# STM32F107_207.net
KiCad netlist of a schematic drawn in Altium Designer
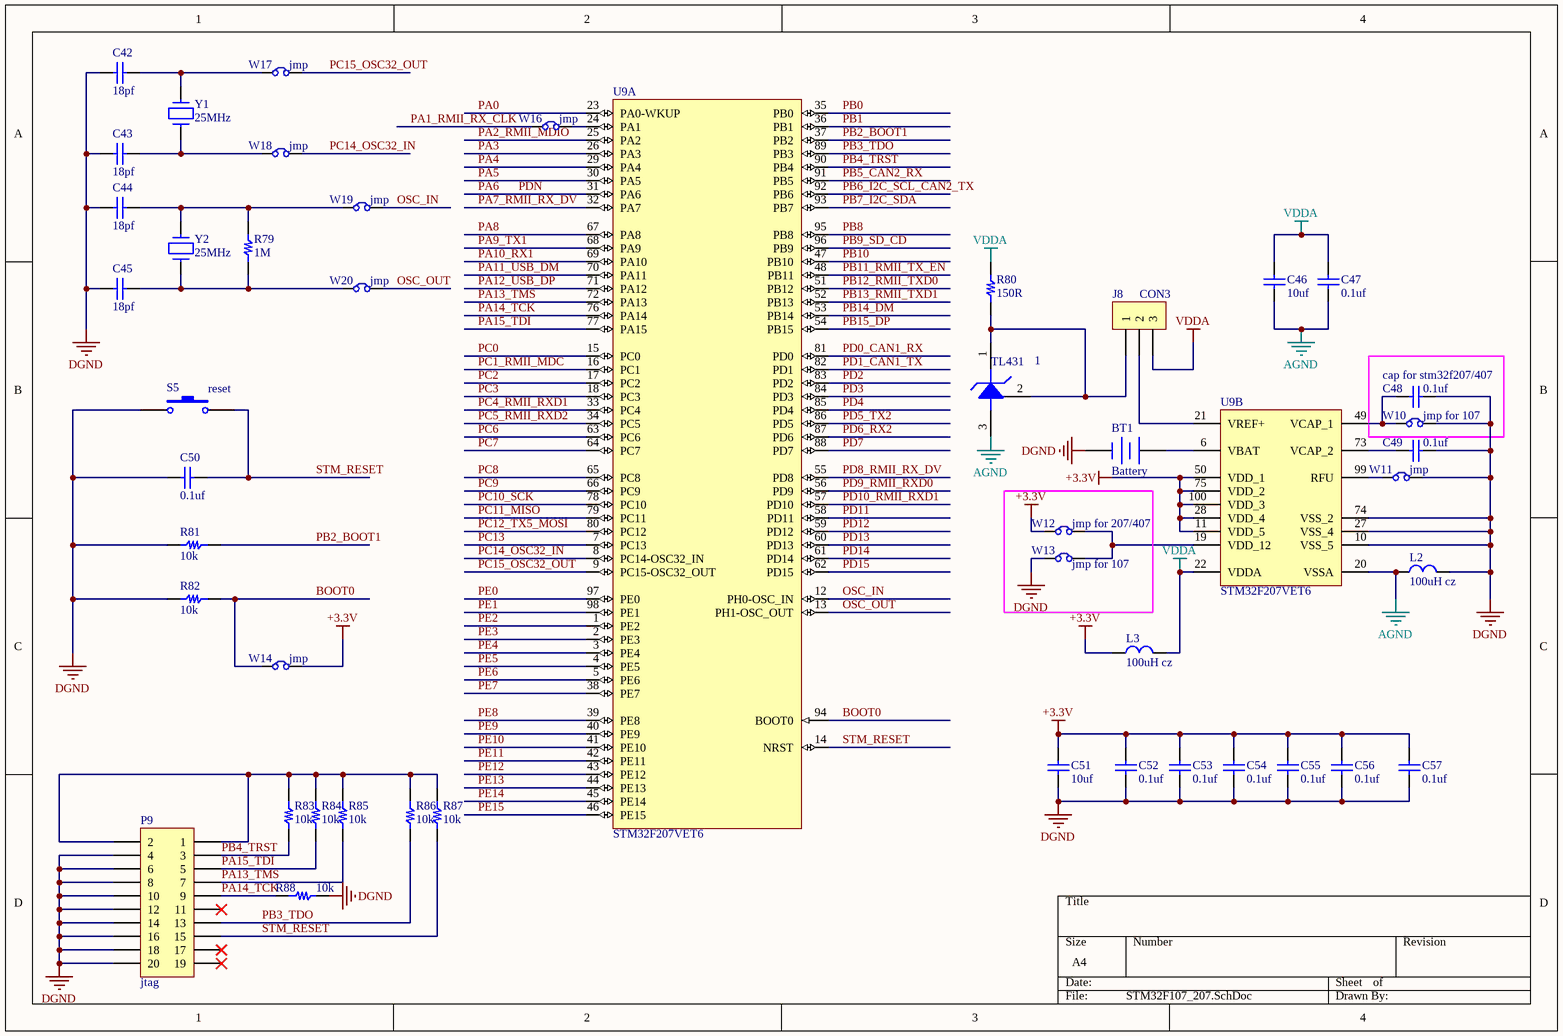
[diagram p0: STM32F107_207.SchDoc]

(export (version "E")
  (design (tool "Eeschema 10.0.6"))
  (components
    (comp (ref "1") (value "TL431") (footprint "SOT23") (libsource (lib "Device_CHT") (part "TL431")))
    (comp (ref "BT1")
      (value "Battery")
      (footprint "CR1220")
      (description "Multicell Battery")
      (fields (field (name "PUBLISHER") "Altium Limited"))
      (libsource (lib "Device_CHT") (part "Battery"))
    )
    (comp (ref "C42")
      (value "18pf")
      (footprint "0805C")
      (description "贴片电容")
      (fields (field (name "PUBLISHER") "Altium Limited"))
      (libsource (lib "Device_CHT") (part "Cap"))
    )
    (comp (ref "C43")
      (value "18pf")
      (footprint "0805C")
      (description "贴片电容")
      (fields (field (name "PUBLISHER") "Altium Limited"))
      (libsource (lib "Device_CHT") (part "Cap"))
    )
    (comp (ref "C44")
      (value "18pf")
      (footprint "0805C")
      (description "贴片电容")
      (fields (field (name "PUBLISHER") "Altium Limited"))
      (libsource (lib "Device_CHT") (part "Cap"))
    )
    (comp (ref "C45")
      (value "18pf")
      (footprint "0805C")
      (description "贴片电容")
      (fields (field (name "PUBLISHER") "Altium Limited"))
      (libsource (lib "Device_CHT") (part "Cap"))
    )
    (comp (ref "C46")
      (value "10uf")
      (footprint "0805C")
      (description "贴片电容")
      (fields (field (name "PUBLISHER") "Altium Limited"))
      (libsource (lib "Device_CHT") (part "Cap"))
    )
    (comp (ref "C47")
      (value "0.1uf")
      (footprint "0805C")
      (description "贴片电容")
      (fields (field (name "PUBLISHER") "Altium Limited"))
      (libsource (lib "Device_CHT") (part "Cap"))
    )
    (comp (ref "C48")
      (value "0.1uf")
      (footprint "0805C")
      (description "贴片电容")
      (fields (field (name "PUBLISHER") "Altium Limited"))
      (libsource (lib "Device_CHT") (part "Cap"))
    )
    (comp (ref "C49")
      (value "0.1uf")
      (footprint "0805C")
      (description "贴片电容")
      (fields (field (name "PUBLISHER") "Altium Limited"))
      (libsource (lib "Device_CHT") (part "Cap"))
    )
    (comp (ref "C50")
      (value "0.1uf")
      (footprint "0805C")
      (description "贴片电容")
      (fields (field (name "PUBLISHER") "Altium Limited"))
      (libsource (lib "Device_CHT") (part "Cap"))
    )
    (comp (ref "C51")
      (value "10uf")
      (footprint "0805C")
      (description "贴片电容")
      (fields (field (name "PUBLISHER") "Altium Limited"))
      (libsource (lib "Device_CHT") (part "Cap"))
    )
    (comp (ref "C52")
      (value "0.1uf")
      (footprint "0805C")
      (description "贴片电容")
      (fields (field (name "PUBLISHER") "Altium Limited"))
      (libsource (lib "Device_CHT") (part "Cap"))
    )
    (comp (ref "C53")
      (value "0.1uf")
      (footprint "0805C")
      (description "贴片电容")
      (fields (field (name "PUBLISHER") "Altium Limited"))
      (libsource (lib "Device_CHT") (part "Cap"))
    )
    (comp (ref "C54")
      (value "0.1uf")
      (footprint "0805C")
      (description "贴片电容")
      (fields (field (name "PUBLISHER") "Altium Limited"))
      (libsource (lib "Device_CHT") (part "Cap"))
    )
    (comp (ref "C55")
      (value "0.1uf")
      (footprint "0805C")
      (description "贴片电容")
      (fields (field (name "PUBLISHER") "Altium Limited"))
      (libsource (lib "Device_CHT") (part "Cap"))
    )
    (comp (ref "C56")
      (value "0.1uf")
      (footprint "0805C")
      (description "贴片电容")
      (fields (field (name "PUBLISHER") "Altium Limited"))
      (libsource (lib "Device_CHT") (part "Cap"))
    )
    (comp (ref "C57")
      (value "0.1uf")
      (footprint "0805C")
      (description "贴片电容")
      (fields (field (name "PUBLISHER") "Altium Limited"))
      (libsource (lib "Device_CHT") (part "Cap"))
    )
    (comp (ref "J8")
      (value "CON3")
      (footprint "sip3-2.54mm")
      (description "Connector")
      (libsource (lib "Connector_Veiko") (part "CON3"))
    )
    (comp (ref "L2")
      (value "100uH cz")
      (footprint "0805_SmallR")
      (description "电感")
      (fields (field (name "PUBLISHER") "Altium Limited"))
      (libsource (lib "Device_CHT") (part "Inductor"))
    )
    (comp (ref "L3")
      (value "100uH cz")
      (footprint "0805_SmallR")
      (description "电感")
      (fields (field (name "PUBLISHER") "Altium Limited"))
      (libsource (lib "Device_CHT") (part "Inductor"))
    )
    (comp (ref "P9")
      (value "jtag")
      (footprint "IDE20-2.54MM")
      (description "Header, 10-Pin, Dual row")
      (fields (field (name "PUBLISHER") "Altium Limited"))
      (libsource (lib "Connector_Veiko") (part "CON10X2"))
    )
    (comp (ref "R79")
      (value "1M")
      (footprint "0805_small")
      (description "电阻")
      (fields (field (name "PUBLISHER") "Altium Limited"))
      (libsource (lib "Device_CHT") (part "Res"))
    )
    (comp (ref "R80")
      (value "150R")
      (footprint "0805_small")
      (description "电阻")
      (fields (field (name "PUBLISHER") "Altium Limited"))
      (libsource (lib "Device_CHT") (part "Res"))
    )
    (comp (ref "R81")
      (value "10k")
      (footprint "0805_small")
      (description "电阻")
      (fields (field (name "PUBLISHER") "Altium Limited"))
      (libsource (lib "Device_CHT") (part "Res"))
    )
    (comp (ref "R82")
      (value "10k")
      (footprint "0805_small")
      (description "电阻")
      (fields (field (name "PUBLISHER") "Altium Limited"))
      (libsource (lib "Device_CHT") (part "Res"))
    )
    (comp (ref "R83")
      (value "10k")
      (footprint "0805_small")
      (description "电阻")
      (fields (field (name "PUBLISHER") "Altium Limited"))
      (libsource (lib "Device_CHT") (part "Res"))
    )
    (comp (ref "R84")
      (value "10k")
      (footprint "0805_small")
      (description "电阻")
      (fields (field (name "PUBLISHER") "Altium Limited"))
      (libsource (lib "Device_CHT") (part "Res"))
    )
    (comp (ref "R85")
      (value "10k")
      (footprint "0805_small")
      (description "电阻")
      (fields (field (name "PUBLISHER") "Altium Limited"))
      (libsource (lib "Device_CHT") (part "Res"))
    )
    (comp (ref "R86")
      (value "10k")
      (footprint "0805_small")
      (description "电阻")
      (fields (field (name "PUBLISHER") "Altium Limited"))
      (libsource (lib "Device_CHT") (part "Res"))
    )
    (comp (ref "R87")
      (value "10k")
      (footprint "0805_small")
      (description "电阻")
      (fields (field (name "PUBLISHER") "Altium Limited"))
      (libsource (lib "Device_CHT") (part "Res"))
    )
    (comp (ref "R88")
      (value "10k")
      (footprint "0805_small")
      (description "电阻")
      (fields (field (name "PUBLISHER") "Altium Limited"))
      (libsource (lib "Device_CHT") (part "Res"))
    )
    (comp (ref "S5")
      (value "reset")
      (footprint "k_TS_021")
      (description "Switch")
      (fields (field (name "PUBLISHER") "Altium Limited"))
      (libsource (lib "Device_CHT") (part "SW-PB-2"))
    )
    (comp (ref "U9")
      (value "STM32F207VET6")
      (footprint "LQFP100_N")
      (libsource (lib "STMicroelectronics STM32 F2") (part "STM32F207VET6"))
    )
    (comp (ref "W10")
      (value "jmp for 107")
      (footprint "0603_jump_Pad")
      (description "Jumper Wire")
      (fields (field (name "PUBLISHER") "Altium Limited"))
      (libsource (lib "Connector_Veiko") (part "Jumper"))
    )
    (comp (ref "W11")
      (value "jmp")
      (footprint "0603_jump_Pad")
      (description "Jumper Wire")
      (fields (field (name "PUBLISHER") "Altium Limited"))
      (libsource (lib "Connector_Veiko") (part "Jumper"))
    )
    (comp (ref "W12")
      (value "jmp for 207/407")
      (footprint "0603_jump_Pad")
      (description "Jumper Wire")
      (fields (field (name "PUBLISHER") "Altium Limited"))
      (libsource (lib "Connector_Veiko") (part "Jumper"))
    )
    (comp (ref "W13")
      (value "jmp for 107")
      (footprint "0603_jump_Pad")
      (description "Jumper Wire")
      (fields (field (name "PUBLISHER") "Altium Limited"))
      (libsource (lib "Connector_Veiko") (part "Jumper"))
    )
    (comp (ref "W14")
      (value "jmp")
      (footprint "0603_jump_Pad")
      (description "Jumper Wire")
      (fields (field (name "PUBLISHER") "Altium Limited"))
      (libsource (lib "Connector_Veiko") (part "Jumper"))
    )
    (comp (ref "W16")
      (value "jmp")
      (footprint "0603_jump_Pad")
      (description "Jumper Wire")
      (fields (field (name "PUBLISHER") "Altium Limited"))
      (libsource (lib "Connector_Veiko") (part "Jumper"))
    )
    (comp (ref "W17")
      (value "jmp")
      (footprint "0603_jump_Pad")
      (description "Jumper Wire")
      (fields (field (name "PUBLISHER") "Altium Limited"))
      (libsource (lib "Connector_Veiko") (part "Jumper"))
    )
    (comp (ref "W18")
      (value "jmp")
      (footprint "0603_jump_Pad")
      (description "Jumper Wire")
      (fields (field (name "PUBLISHER") "Altium Limited"))
      (libsource (lib "Connector_Veiko") (part "Jumper"))
    )
    (comp (ref "W19")
      (value "jmp")
      (footprint "0603_jump_Pad")
      (description "Jumper Wire")
      (fields (field (name "PUBLISHER") "Altium Limited"))
      (libsource (lib "Connector_Veiko") (part "Jumper"))
    )
    (comp (ref "W20")
      (value "jmp")
      (footprint "0603_jump_Pad")
      (description "Jumper Wire")
      (fields (field (name "PUBLISHER") "Altium Limited"))
      (libsource (lib "Connector_Veiko") (part "Jumper"))
    )
    (comp (ref "Y1")
      (value "25MHz")
      (footprint "CRY 32768-1")
      (description "JZ")
      (libsource (lib "Device_CHT") (part "CRYSTAL"))
    )
    (comp (ref "Y2")
      (value "25MHz")
      (footprint "CRYSTAL")
      (description "JZ")
      (libsource (lib "Device_CHT") (part "CRYSTAL"))
    )
  )
  (nets
    (net (code "1") (name "+3.3V") (class "Default")
      (node (ref "C51") (pin "1") (pinfunction "1_1") (pintype "passive"))
      (node (ref "C52") (pin "1") (pinfunction "1_1") (pintype "passive"))
      (node (ref "C53") (pin "1") (pinfunction "1_1") (pintype "passive"))
      (node (ref "C54") (pin "1") (pinfunction "1_1") (pintype "passive"))
      (node (ref "C55") (pin "1") (pinfunction "1_1") (pintype "passive"))
      (node (ref "C56") (pin "1") (pinfunction "1_1") (pintype "passive"))
      (node (ref "C57") (pin "1") (pinfunction "1_1") (pintype "passive"))
      (node (ref "L3") (pin "1") (pinfunction "1_1") (pintype "passive"))
      (node (ref "U9") (pin "100") (pinfunction "VDD_3_100") (pintype "power_in"))
      (node (ref "U9") (pin "11") (pinfunction "VDD_5_11") (pintype "power_in"))
      (node (ref "U9") (pin "28") (pinfunction "VDD_4_28") (pintype "power_in"))
      (node (ref "U9") (pin "50") (pinfunction "VDD_1_50") (pintype "power_in"))
      (node (ref "U9") (pin "75") (pinfunction "VDD_2_75") (pintype "power_in"))
      (node (ref "W12") (pin "1") (pinfunction "C1_1") (pintype "passive"))
      (node (ref "W14") (pin "2") (pinfunction "C2_2") (pintype "passive"))
    )
    (net (code "2") (name "/BOOT0") (class "Default")
      (node (ref "R82") (pin "1") (pinfunction "1_1") (pintype "passive"))
      (node (ref "U9") (pin "94") (pinfunction "BOOT0_94") (pintype "input"))
      (node (ref "W14") (pin "1") (pinfunction "C1_1") (pintype "passive"))
    )
    (net (code "3") (name "/OSC_IN") (class "Default")
      (node (ref "U9") (pin "12") (pinfunction "PH0-OSC_IN_12") (pintype "bidirectional"))
      (node (ref "W19") (pin "2") (pinfunction "C2_2") (pintype "passive"))
    )
    (net (code "4") (name "/OSC_OUT") (class "Default")
      (node (ref "U9") (pin "13") (pinfunction "PH1-OSC_OUT_13") (pintype "bidirectional"))
      (node (ref "W20") (pin "2") (pinfunction "C2_2") (pintype "passive"))
    )
    (net (code "5") (name "/PA0") (class "Default")
      (node (ref "U9") (pin "23") (pinfunction "PA0-WKUP_23") (pintype "bidirectional"))
    )
    (net (code "6") (name "/PA1_RMII_RX_CLK") (class "Default")
      (node (ref "W16") (pin "1") (pinfunction "C1_1") (pintype "passive"))
    )
    (net (code "7") (name "/PA2_RMII_MDIO") (class "Default")
      (node (ref "U9") (pin "25") (pinfunction "PA2_25") (pintype "bidirectional"))
    )
    (net (code "8") (name "/PA3") (class "Default")
      (node (ref "U9") (pin "26") (pinfunction "PA3_26") (pintype "bidirectional"))
    )
    (net (code "9") (name "/PA4") (class "Default")
      (node (ref "U9") (pin "29") (pinfunction "PA4_29") (pintype "bidirectional"))
    )
    (net (code "10") (name "/PA5") (class "Default")
      (node (ref "U9") (pin "30") (pinfunction "PA5_30") (pintype "bidirectional"))
    )
    (net (code "11") (name "/PA6") (class "Default")
      (node (ref "U9") (pin "31") (pinfunction "PA6_31") (pintype "bidirectional"))
    )
    (net (code "12") (name "/PA7_RMII_RX_DV") (class "Default")
      (node (ref "U9") (pin "32") (pinfunction "PA7_32") (pintype "bidirectional"))
    )
    (net (code "13") (name "/PA8") (class "Default")
      (node (ref "U9") (pin "67") (pinfunction "PA8_67") (pintype "bidirectional"))
    )
    (net (code "14") (name "/PA9_TX1") (class "Default")
      (node (ref "U9") (pin "68") (pinfunction "PA9_68") (pintype "bidirectional"))
    )
    (net (code "15") (name "/PA10_RX1") (class "Default")
      (node (ref "U9") (pin "69") (pinfunction "PA10_69") (pintype "bidirectional"))
    )
    (net (code "16") (name "/PA11_USB_DM") (class "Default")
      (node (ref "U9") (pin "70") (pinfunction "PA11_70") (pintype "bidirectional"))
    )
    (net (code "17") (name "/PA12_USB_DP") (class "Default")
      (node (ref "U9") (pin "71") (pinfunction "PA12_71") (pintype "bidirectional"))
    )
    (net (code "18") (name "/PA13_TMS") (class "Default")
      (node (ref "P9") (pin "7") (pinfunction "7_7") (pintype "passive"))
      (node (ref "R85") (pin "2") (pinfunction "2_2") (pintype "passive"))
      (node (ref "U9") (pin "72") (pinfunction "PA13_72") (pintype "bidirectional"))
    )
    (net (code "19") (name "/PA14_TCK") (class "Default")
      (node (ref "P9") (pin "9") (pinfunction "9_9") (pintype "passive"))
      (node (ref "R88") (pin "1") (pinfunction "1_1") (pintype "passive"))
      (node (ref "U9") (pin "76") (pinfunction "PA14_76") (pintype "bidirectional"))
    )
    (net (code "20") (name "/PA15_TDI") (class "Default")
      (node (ref "P9") (pin "5") (pinfunction "5_5") (pintype "passive"))
      (node (ref "R84") (pin "2") (pinfunction "2_2") (pintype "passive"))
      (node (ref "U9") (pin "77") (pinfunction "PA15_77") (pintype "bidirectional"))
    )
    (net (code "21") (name "/PB0") (class "Default")
      (node (ref "U9") (pin "35") (pinfunction "PB0_35") (pintype "bidirectional"))
    )
    (net (code "22") (name "/PB1") (class "Default")
      (node (ref "U9") (pin "36") (pinfunction "PB1_36") (pintype "bidirectional"))
    )
    (net (code "23") (name "/PB2_BOOT1") (class "Default")
      (node (ref "R81") (pin "1") (pinfunction "1_1") (pintype "passive"))
      (node (ref "U9") (pin "37") (pinfunction "PB2_37") (pintype "bidirectional"))
    )
    (net (code "24") (name "/PB3_TDO") (class "Default")
      (node (ref "P9") (pin "13") (pinfunction "13_13") (pintype "passive"))
      (node (ref "R86") (pin "2") (pinfunction "2_2") (pintype "passive"))
      (node (ref "U9") (pin "89") (pinfunction "PB3_89") (pintype "bidirectional"))
    )
    (net (code "25") (name "/PB4_TRST") (class "Default")
      (node (ref "P9") (pin "3") (pinfunction "3_3") (pintype "passive"))
      (node (ref "R83") (pin "2") (pinfunction "2_2") (pintype "passive"))
      (node (ref "U9") (pin "90") (pinfunction "PB4_90") (pintype "bidirectional"))
    )
    (net (code "26") (name "/PB5_CAN2_RX") (class "Default")
      (node (ref "U9") (pin "91") (pinfunction "PB5_91") (pintype "bidirectional"))
    )
    (net (code "27") (name "/PB6_I2C_SCL_CAN2_TX") (class "Default")
      (node (ref "U9") (pin "92") (pinfunction "PB6_92") (pintype "bidirectional"))
    )
    (net (code "28") (name "/PB7_I2C_SDA") (class "Default")
      (node (ref "U9") (pin "93") (pinfunction "PB7_93") (pintype "bidirectional"))
    )
    (net (code "29") (name "/PB8") (class "Default")
      (node (ref "U9") (pin "95") (pinfunction "PB8_95") (pintype "bidirectional"))
    )
    (net (code "30") (name "/PB9_SD_CD") (class "Default")
      (node (ref "U9") (pin "96") (pinfunction "PB9_96") (pintype "bidirectional"))
    )
    (net (code "31") (name "/PB10") (class "Default")
      (node (ref "U9") (pin "47") (pinfunction "PB10_47") (pintype "bidirectional"))
    )
    (net (code "32") (name "/PB11_RMII_TX_EN") (class "Default")
      (node (ref "U9") (pin "48") (pinfunction "PB11_48") (pintype "bidirectional"))
    )
    (net (code "33") (name "/PB12_RMII_TXD0") (class "Default")
      (node (ref "U9") (pin "51") (pinfunction "PB12_51") (pintype "bidirectional"))
    )
    (net (code "34") (name "/PB13_RMII_TXD1") (class "Default")
      (node (ref "U9") (pin "52") (pinfunction "PB13_52") (pintype "bidirectional"))
    )
    (net (code "35") (name "/PB14_DM") (class "Default")
      (node (ref "U9") (pin "53") (pinfunction "PB14_53") (pintype "bidirectional"))
    )
    (net (code "36") (name "/PB15_DP") (class "Default")
      (node (ref "U9") (pin "54") (pinfunction "PB15_54") (pintype "bidirectional"))
    )
    (net (code "37") (name "/PC0") (class "Default")
      (node (ref "U9") (pin "15") (pinfunction "PC0_15") (pintype "bidirectional"))
    )
    (net (code "38") (name "/PC1_RMII_MDC") (class "Default")
      (node (ref "U9") (pin "16") (pinfunction "PC1_16") (pintype "bidirectional"))
    )
    (net (code "39") (name "/PC2") (class "Default")
      (node (ref "U9") (pin "17") (pinfunction "PC2_17") (pintype "bidirectional"))
    )
    (net (code "40") (name "/PC3") (class "Default")
      (node (ref "U9") (pin "18") (pinfunction "PC3_18") (pintype "bidirectional"))
    )
    (net (code "41") (name "/PC4_RMII_RXD1") (class "Default")
      (node (ref "U9") (pin "33") (pinfunction "PC4_33") (pintype "bidirectional"))
    )
    (net (code "42") (name "/PC5_RMII_RXD2") (class "Default")
      (node (ref "U9") (pin "34") (pinfunction "PC5_34") (pintype "bidirectional"))
    )
    (net (code "43") (name "/PC6") (class "Default")
      (node (ref "U9") (pin "63") (pinfunction "PC6_63") (pintype "bidirectional"))
    )
    (net (code "44") (name "/PC7") (class "Default")
      (node (ref "U9") (pin "64") (pinfunction "PC7_64") (pintype "bidirectional"))
    )
    (net (code "45") (name "/PC8") (class "Default")
      (node (ref "U9") (pin "65") (pinfunction "PC8_65") (pintype "bidirectional"))
    )
    (net (code "46") (name "/PC9") (class "Default")
      (node (ref "U9") (pin "66") (pinfunction "PC9_66") (pintype "bidirectional"))
    )
    (net (code "47") (name "/PC10_SCK") (class "Default")
      (node (ref "U9") (pin "78") (pinfunction "PC10_78") (pintype "bidirectional"))
    )
    (net (code "48") (name "/PC11_MISO") (class "Default")
      (node (ref "U9") (pin "79") (pinfunction "PC11_79") (pintype "bidirectional"))
    )
    (net (code "49") (name "/PC12_TX5_MOSI") (class "Default")
      (node (ref "U9") (pin "80") (pinfunction "PC12_80") (pintype "bidirectional"))
    )
    (net (code "50") (name "/PC13") (class "Default")
      (node (ref "U9") (pin "7") (pinfunction "PC13_7") (pintype "bidirectional"))
    )
    (net (code "51") (name "/PC14_OSC32_IN") (class "Default")
      (node (ref "U9") (pin "8") (pinfunction "PC14-OSC32_IN_8") (pintype "bidirectional"))
      (node (ref "W18") (pin "2") (pinfunction "C2_2") (pintype "passive"))
    )
    (net (code "52") (name "/PC15_OSC32_OUT") (class "Default")
      (node (ref "U9") (pin "9") (pinfunction "PC15-OSC32_OUT_9") (pintype "bidirectional"))
      (node (ref "W17") (pin "2") (pinfunction "C2_2") (pintype "passive"))
    )
    (net (code "53") (name "/PD0_CAN1_RX") (class "Default")
      (node (ref "U9") (pin "81") (pinfunction "PD0_81") (pintype "bidirectional"))
    )
    (net (code "54") (name "/PD1_CAN1_TX") (class "Default")
      (node (ref "U9") (pin "82") (pinfunction "PD1_82") (pintype "bidirectional"))
    )
    (net (code "55") (name "/PD2") (class "Default")
      (node (ref "U9") (pin "83") (pinfunction "PD2_83") (pintype "bidirectional"))
    )
    (net (code "56") (name "/PD3") (class "Default")
      (node (ref "U9") (pin "84") (pinfunction "PD3_84") (pintype "bidirectional"))
    )
    (net (code "57") (name "/PD4") (class "Default")
      (node (ref "U9") (pin "85") (pinfunction "PD4_85") (pintype "bidirectional"))
    )
    (net (code "58") (name "/PD5_TX2") (class "Default")
      (node (ref "U9") (pin "86") (pinfunction "PD5_86") (pintype "bidirectional"))
    )
    (net (code "59") (name "/PD6_RX2") (class "Default")
      (node (ref "U9") (pin "87") (pinfunction "PD6_87") (pintype "bidirectional"))
    )
    (net (code "60") (name "/PD7") (class "Default")
      (node (ref "U9") (pin "88") (pinfunction "PD7_88") (pintype "bidirectional"))
    )
    (net (code "61") (name "/PD8_RMII_RX_DV") (class "Default")
      (node (ref "U9") (pin "55") (pinfunction "PD8_55") (pintype "bidirectional"))
    )
    (net (code "62") (name "/PD9_RMII_RXD0") (class "Default")
      (node (ref "U9") (pin "56") (pinfunction "PD9_56") (pintype "bidirectional"))
    )
    (net (code "63") (name "/PD10_RMII_RXD1") (class "Default")
      (node (ref "U9") (pin "57") (pinfunction "PD10_57") (pintype "bidirectional"))
    )
    (net (code "64") (name "/PD11") (class "Default")
      (node (ref "U9") (pin "58") (pinfunction "PD11_58") (pintype "bidirectional"))
    )
    (net (code "65") (name "/PD12") (class "Default")
      (node (ref "U9") (pin "59") (pinfunction "PD12_59") (pintype "bidirectional"))
    )
    (net (code "66") (name "/PD13") (class "Default")
      (node (ref "U9") (pin "60") (pinfunction "PD13_60") (pintype "bidirectional"))
    )
    (net (code "67") (name "/PD14") (class "Default")
      (node (ref "U9") (pin "61") (pinfunction "PD14_61") (pintype "bidirectional"))
    )
    (net (code "68") (name "/PD15") (class "Default")
      (node (ref "U9") (pin "62") (pinfunction "PD15_62") (pintype "bidirectional"))
    )
    (net (code "69") (name "/PE0") (class "Default")
      (node (ref "U9") (pin "97") (pinfunction "PE0_97") (pintype "bidirectional"))
    )
    (net (code "70") (name "/PE1") (class "Default")
      (node (ref "U9") (pin "98") (pinfunction "PE1_98") (pintype "bidirectional"))
    )
    (net (code "71") (name "/PE2") (class "Default")
      (node (ref "U9") (pin "1") (pinfunction "PE2_1") (pintype "bidirectional"))
    )
    (net (code "72") (name "/PE3") (class "Default")
      (node (ref "U9") (pin "2") (pinfunction "PE3_2") (pintype "bidirectional"))
    )
    (net (code "73") (name "/PE4") (class "Default")
      (node (ref "U9") (pin "3") (pinfunction "PE4_3") (pintype "bidirectional"))
    )
    (net (code "74") (name "/PE5") (class "Default")
      (node (ref "U9") (pin "4") (pinfunction "PE5_4") (pintype "bidirectional"))
    )
    (net (code "75") (name "/PE6") (class "Default")
      (node (ref "U9") (pin "5") (pinfunction "PE6_5") (pintype "bidirectional"))
    )
    (net (code "76") (name "/PE7") (class "Default")
      (node (ref "U9") (pin "38") (pinfunction "PE7_38") (pintype "bidirectional"))
    )
    (net (code "77") (name "/PE8") (class "Default")
      (node (ref "U9") (pin "39") (pinfunction "PE8_39") (pintype "bidirectional"))
    )
    (net (code "78") (name "/PE9") (class "Default")
      (node (ref "U9") (pin "40") (pinfunction "PE9_40") (pintype "bidirectional"))
    )
    (net (code "79") (name "/PE10") (class "Default")
      (node (ref "U9") (pin "41") (pinfunction "PE10_41") (pintype "bidirectional"))
    )
    (net (code "80") (name "/PE11") (class "Default")
      (node (ref "U9") (pin "42") (pinfunction "PE11_42") (pintype "bidirectional"))
    )
    (net (code "81") (name "/PE12") (class "Default")
      (node (ref "U9") (pin "43") (pinfunction "PE12_43") (pintype "bidirectional"))
    )
    (net (code "82") (name "/PE13") (class "Default")
      (node (ref "U9") (pin "44") (pinfunction "PE13_44") (pintype "bidirectional"))
    )
    (net (code "83") (name "/PE14") (class "Default")
      (node (ref "U9") (pin "45") (pinfunction "PE14_45") (pintype "bidirectional"))
    )
    (net (code "84") (name "/PE15") (class "Default")
      (node (ref "U9") (pin "46") (pinfunction "PE15_46") (pintype "bidirectional"))
    )
    (net (code "85") (name "/STM_RESET") (class "Default")
      (node (ref "C50") (pin "1") (pinfunction "1_1") (pintype "passive"))
      (node (ref "P9") (pin "15") (pinfunction "15_15") (pintype "passive"))
      (node (ref "R87") (pin "2") (pinfunction "2_2") (pintype "passive"))
      (node (ref "S5") (pin "2") (pinfunction "2_2") (pintype "passive"))
      (node (ref "U9") (pin "14") (pinfunction "NRST_14") (pintype "bidirectional"))
    )
    (net (code "86") (name "AGND") (class "Default")
      (node (ref "1") (pin "3") (pinfunction "ANODE_3") (pintype "passive"))
      (node (ref "C46") (pin "1") (pinfunction "1_1") (pintype "passive"))
      (node (ref "C47") (pin "1") (pinfunction "1_1") (pintype "passive"))
      (node (ref "L2") (pin "1") (pinfunction "1_1") (pintype "passive"))
      (node (ref "U9") (pin "20") (pinfunction "VSSA_20") (pintype "power_in"))
    )
    (net (code "87") (name "DGND") (class "Default")
      (node (ref "BT1") (pin "2") (pinfunction "-_2") (pintype "passive"))
      (node (ref "C42") (pin "2") (pinfunction "2_2") (pintype "passive"))
      (node (ref "C43") (pin "2") (pinfunction "2_2") (pintype "passive"))
      (node (ref "C44") (pin "2") (pinfunction "2_2") (pintype "passive"))
      (node (ref "C45") (pin "2") (pinfunction "2_2") (pintype "passive"))
      (node (ref "C48") (pin "1") (pinfunction "1_1") (pintype "passive"))
      (node (ref "C49") (pin "1") (pinfunction "1_1") (pintype "passive"))
      (node (ref "C50") (pin "2") (pinfunction "2_2") (pintype "passive"))
      (node (ref "C51") (pin "2") (pinfunction "2_2") (pintype "passive"))
      (node (ref "C52") (pin "2") (pinfunction "2_2") (pintype "passive"))
      (node (ref "C53") (pin "2") (pinfunction "2_2") (pintype "passive"))
      (node (ref "C54") (pin "2") (pinfunction "2_2") (pintype "passive"))
      (node (ref "C55") (pin "2") (pinfunction "2_2") (pintype "passive"))
      (node (ref "C56") (pin "2") (pinfunction "2_2") (pintype "passive"))
      (node (ref "C57") (pin "2") (pinfunction "2_2") (pintype "passive"))
      (node (ref "L2") (pin "2") (pinfunction "2_2") (pintype "passive"))
      (node (ref "P9") (pin "10") (pinfunction "10_10") (pintype "passive"))
      (node (ref "P9") (pin "12") (pinfunction "12_12") (pintype "passive"))
      (node (ref "P9") (pin "14") (pinfunction "14_14") (pintype "passive"))
      (node (ref "P9") (pin "16") (pinfunction "16_16") (pintype "passive"))
      (node (ref "P9") (pin "18") (pinfunction "18_18") (pintype "passive"))
      (node (ref "P9") (pin "20") (pinfunction "20_20") (pintype "passive"))
      (node (ref "P9") (pin "4") (pinfunction "4_4") (pintype "passive"))
      (node (ref "P9") (pin "6") (pinfunction "6_6") (pintype "passive"))
      (node (ref "P9") (pin "8") (pinfunction "8_8") (pintype "passive"))
      (node (ref "R81") (pin "2") (pinfunction "2_2") (pintype "passive"))
      (node (ref "R82") (pin "2") (pinfunction "2_2") (pintype "passive"))
      (node (ref "R88") (pin "2") (pinfunction "2_2") (pintype "passive"))
      (node (ref "S5") (pin "1") (pinfunction "1_1") (pintype "passive"))
      (node (ref "U9") (pin "10") (pinfunction "VSS_5_10") (pintype "power_in"))
      (node (ref "U9") (pin "27") (pinfunction "VSS_4_27") (pintype "power_in"))
      (node (ref "U9") (pin "74") (pinfunction "VSS_2_74") (pintype "power_in"))
      (node (ref "W10") (pin "2") (pinfunction "C2_2") (pintype "passive"))
      (node (ref "W11") (pin "2") (pinfunction "C2_2") (pintype "passive"))
      (node (ref "W13") (pin "1") (pinfunction "C1_1") (pintype "passive"))
    )
    (net (code "88") (name "Net-(1-CATHODE)") (class "Default")
      (node (ref "1") (pin "1") (pinfunction "CATHODE_1") (pintype "passive"))
      (node (ref "1") (pin "2") (pinfunction "REF_2") (pintype "passive"))
      (node (ref "J8") (pin "1") (pinfunction "1_1") (pintype "passive"))
      (node (ref "R80") (pin "1") (pinfunction "1_1") (pintype "passive"))
    )
    (net (code "89") (name "Net-(BT1-+)") (class "Default")
      (node (ref "BT1") (pin "1") (pinfunction "+_1") (pintype "passive"))
      (node (ref "U9") (pin "6") (pinfunction "VBAT_6") (pintype "power_in"))
    )
    (net (code "90") (name "Net-(P9-Pad1)") (class "Default")
      (node (ref "P9") (pin "1") (pinfunction "1_1") (pintype "passive"))
      (node (ref "P9") (pin "2") (pinfunction "2_2") (pintype "passive"))
      (node (ref "R83") (pin "1") (pinfunction "1_1") (pintype "passive"))
      (node (ref "R84") (pin "1") (pinfunction "1_1") (pintype "passive"))
      (node (ref "R85") (pin "1") (pinfunction "1_1") (pintype "passive"))
      (node (ref "R86") (pin "1") (pinfunction "1_1") (pintype "passive"))
      (node (ref "R87") (pin "1") (pinfunction "1_1") (pintype "passive"))
    )
    (net (code "91") (name "Net-(U9A-PA1)") (class "Default")
      (node (ref "U9") (pin "24") (pinfunction "PA1_24") (pintype "bidirectional"))
      (node (ref "W16") (pin "2") (pinfunction "C2_2") (pintype "passive"))
    )
    (net (code "92") (name "Net-(U9B-RFU)") (class "Default")
      (node (ref "U9") (pin "99") (pinfunction "RFU_99") (pintype "passive"))
      (node (ref "W11") (pin "1") (pinfunction "C1_1") (pintype "passive"))
    )
    (net (code "93") (name "Net-(U9B-VCAP_1)") (class "Default")
      (node (ref "C48") (pin "2") (pinfunction "2_2") (pintype "passive"))
      (node (ref "U9") (pin "49") (pinfunction "VCAP_1_49") (pintype "power_in"))
      (node (ref "W10") (pin "1") (pinfunction "C1_1") (pintype "passive"))
    )
    (net (code "94") (name "Net-(U9B-VCAP_2)") (class "Default")
      (node (ref "C49") (pin "2") (pinfunction "2_2") (pintype "passive"))
      (node (ref "U9") (pin "73") (pinfunction "VCAP_2_73") (pintype "power_in"))
    )
    (net (code "95") (name "Net-(U9B-VDD_12)") (class "Default")
      (node (ref "U9") (pin "19") (pinfunction "VDD_12_19") (pintype "power_in"))
      (node (ref "W12") (pin "2") (pinfunction "C2_2") (pintype "passive"))
      (node (ref "W13") (pin "2") (pinfunction "C2_2") (pintype "passive"))
    )
    (net (code "96") (name "Net-(U9B-VREF+)") (class "Default")
      (node (ref "J8") (pin "2") (pinfunction "2_2") (pintype "passive"))
      (node (ref "U9") (pin "21") (pinfunction "VREF+_21") (pintype "power_in"))
    )
    (net (code "97") (name "Net-(W17-C1)") (class "Default")
      (node (ref "C42") (pin "1") (pinfunction "1_1") (pintype "passive"))
      (node (ref "W17") (pin "1") (pinfunction "C1_1") (pintype "passive"))
      (node (ref "Y1") (pin "2") (pinfunction "2_2") (pintype "passive"))
    )
    (net (code "98") (name "Net-(W18-C1)") (class "Default")
      (node (ref "C43") (pin "1") (pinfunction "1_1") (pintype "passive"))
      (node (ref "W18") (pin "1") (pinfunction "C1_1") (pintype "passive"))
      (node (ref "Y1") (pin "1") (pinfunction "1_1") (pintype "passive"))
    )
    (net (code "99") (name "Net-(W19-C1)") (class "Default")
      (node (ref "C44") (pin "1") (pinfunction "1_1") (pintype "passive"))
      (node (ref "R79") (pin "2") (pinfunction "2_2") (pintype "passive"))
      (node (ref "W19") (pin "1") (pinfunction "C1_1") (pintype "passive"))
      (node (ref "Y2") (pin "2") (pinfunction "2_2") (pintype "passive"))
    )
    (net (code "100") (name "Net-(W20-C1)") (class "Default")
      (node (ref "C45") (pin "1") (pinfunction "1_1") (pintype "passive"))
      (node (ref "R79") (pin "1") (pinfunction "1_1") (pintype "passive"))
      (node (ref "W20") (pin "1") (pinfunction "C1_1") (pintype "passive"))
      (node (ref "Y2") (pin "1") (pinfunction "1_1") (pintype "passive"))
    )
    (net (code "101") (name "VDDA") (class "Default")
      (node (ref "C46") (pin "2") (pinfunction "2_2") (pintype "passive"))
      (node (ref "C47") (pin "2") (pinfunction "2_2") (pintype "passive"))
      (node (ref "J8") (pin "3") (pinfunction "3_3") (pintype "passive"))
      (node (ref "L3") (pin "2") (pinfunction "2_2") (pintype "passive"))
      (node (ref "R80") (pin "2") (pinfunction "2_2") (pintype "passive"))
      (node (ref "U9") (pin "22") (pinfunction "VDDA_22") (pintype "power_in"))
    )
    (net (code "102") (name "unconnected-(P9-Pad11)") (class "Default")
      (node (ref "P9") (pin "11") (pinfunction "11_11") (pintype "passive+no_connect"))
    )
    (net (code "103") (name "unconnected-(P9-Pad17)") (class "Default")
      (node (ref "P9") (pin "17") (pinfunction "17_17") (pintype "passive+no_connect"))
    )
    (net (code "104") (name "unconnected-(P9-Pad19)") (class "Default")
      (node (ref "P9") (pin "19") (pinfunction "19_19") (pintype "passive+no_connect"))
    )
  )
)
